# 22_Nvidia_CAN.net
KiCad netlist of a schematic drawn in Altium Designer
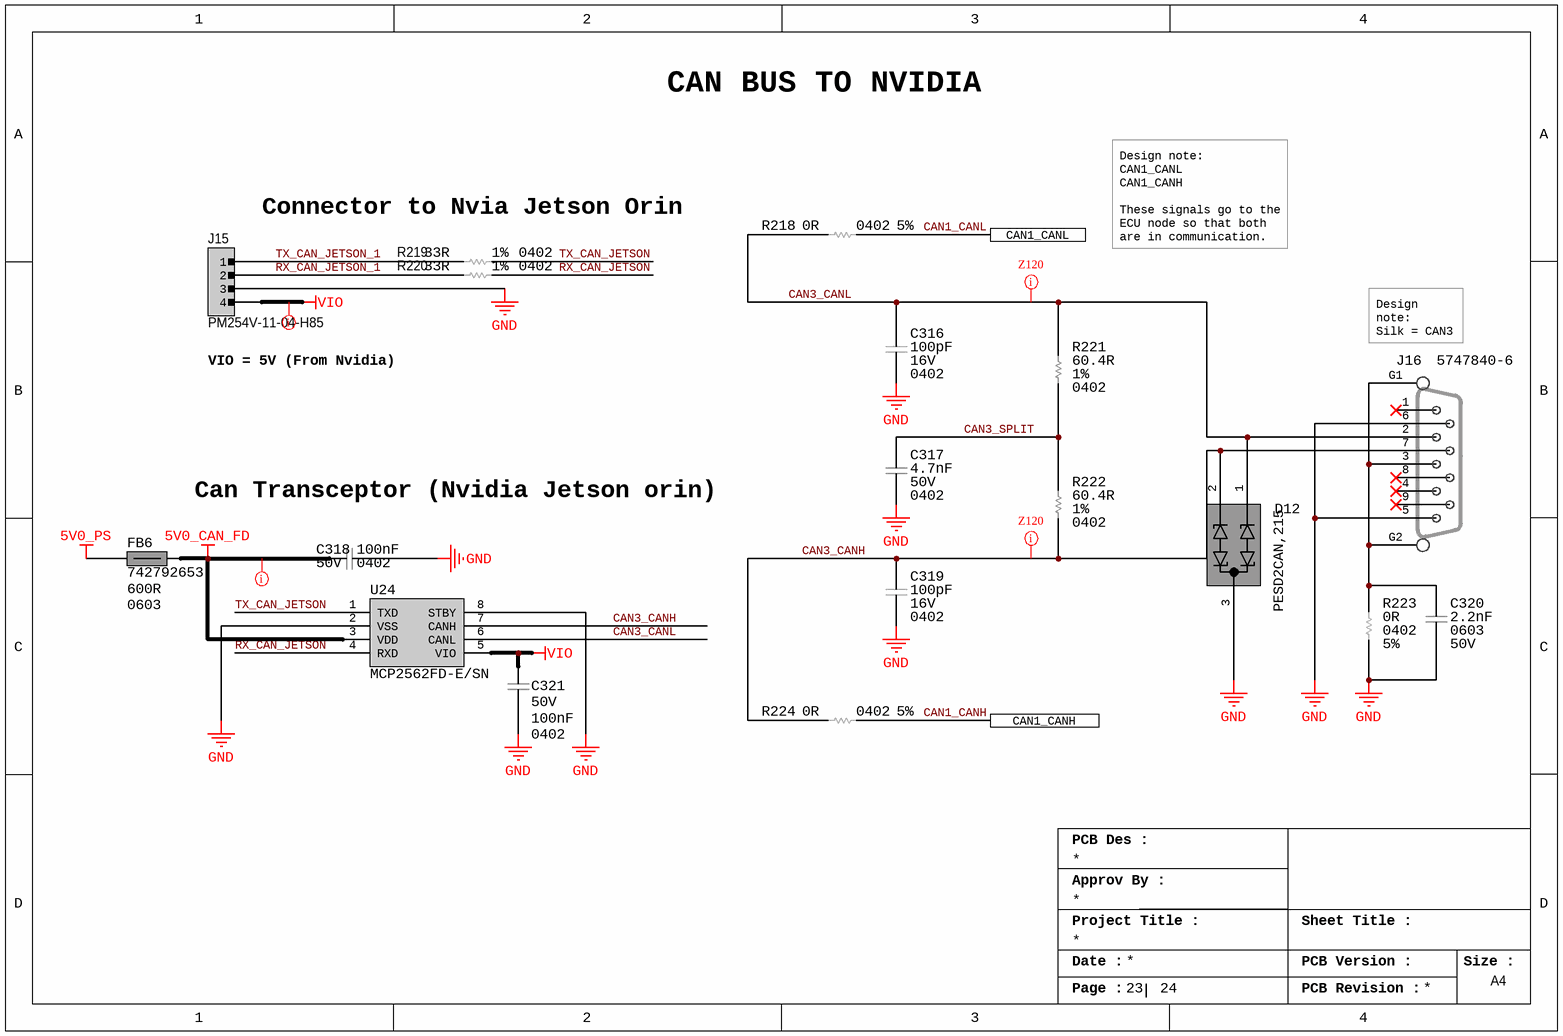
[diagram p0: 22_Nvidia_CAN.SchDoc]

(export (version "E")
  (design (tool "Eeschema 10.0.6"))
  (components
    (comp (ref "C316")
      (value "CC0402JRNPO7BN101")
      (footprint "CAP_0402_CAPC1005X05N")
      (description "0402 100 pF 16 V ±5 % Tolerance NP0 SMT Multilayer Ceramic Capacitor")
      (fields
        (field (name "MANUFACTURER") "Yageo")
        (field (name "TOLERANCE") "5%")
        (field (name "VOLTAGE RATING (DC)") "16V")
        (field (name "CAPACITANCE") "100pF")
        (field (name "CASE/PACKAGE") "0402")
      )
      (libsource (lib "Electronic Devices_LIB") (part "CAP_100PF_16V_NP0_0402"))
    )
    (comp (ref "C317")
      (value "GRM155R61H472KA01D")
      (footprint "CAP_0402_CAPC1005X05N")
      (description "Multilayer Ceramic Capacitor, 100 uF, 16 V, ± 20%, X5R, 1210 [3225 Metric]")
      (fields
        (field (name "MANUFACTURER") "Murata")
        (field (name "TOLERANCE") "10%")
        (field (name "VOLTAGE RATING") "50V")
        (field (name "CAPACITANCE") "4.7nF")
        (field (name "CASE/PACKAGE") "0402")
      )
      (libsource (lib "Electronic Devices_LIB") (part "CAP_4700PF_50V_X5R_0402"))
    )
    (comp (ref "C318")
      (value "GRM155R71H104KE14D")
      (footprint "CAP_0402_CAPC1005X05N")
      (description "Multilayer Ceramic Capacitor, 0.1 uF, 16 V, ± 10%, X7R, 0402 [1005 Metric]")
      (fields
        (field (name "MANUFACTURER") "Murata")
        (field (name "TOLERANCE") "10%")
        (field (name "VOLTAGE RATING") "50V")
        (field (name "CAPACITANCE") "100nF")
        (field (name "CASE/PACKAGE") "0402")
      )
      (libsource (lib "Electronic Devices_LIB") (part "CAP_100NF_50V_X7R_0402"))
    )
    (comp (ref "C319")
      (value "CC0402JRNPO7BN101")
      (footprint "CAP_0402_CAPC1005X05N")
      (description "0402 100 pF 16 V ±5 % Tolerance NP0 SMT Multilayer Ceramic Capacitor")
      (fields
        (field (name "MANUFACTURER") "Yageo")
        (field (name "TOLERANCE") "5%")
        (field (name "VOLTAGE RATING (DC)") "16V")
        (field (name "CAPACITANCE") "100pF")
        (field (name "CASE/PACKAGE") "0402")
      )
      (libsource (lib "Electronic Devices_LIB") (part "CAP_100PF_16V_NP0_0402"))
    )
    (comp (ref "C320")
      (value "GRM1885C1H222JA01D")
      (footprint "CAP_0603_CAPC1608X08N")
      (description "Multilayer Ceramic Capacitor, 2200 pF, 50 V, ï¿½ 5%, C0G (NP0), 0603 [1608 Metric]")
      (fields
        (field (name "MANUFACTURER") "Murata")
        (field (name "TOLERANCE") "5%")
        (field (name "CASE/PACKAGE") "0603")
        (field (name "VOLTAGE RATING") "50V")
        (field (name "CAPACITANCE") "2.2nF")
      )
      (libsource (lib "Electronic Devices_LIB") (part "CAP_2.2nF_50V_NP0_0402"))
    )
    (comp (ref "C321")
      (value "GRM155R71H104KE14D")
      (footprint "CAP_0402_CAPC1005X05N")
      (description "Multilayer Ceramic Capacitor, 0.1 uF, 16 V, ± 10%, X7R, 0402 [1005 Metric]")
      (fields
        (field (name "MANUFACTURER") "Murata")
        (field (name "TOLERANCE") "10%")
        (field (name "VOLTAGE RATING") "50V")
        (field (name "CAPACITANCE") "100nF")
        (field (name "CASE/PACKAGE") "0402")
      )
      (libsource (lib "Electronic Devices_LIB") (part "CAP_100NF_50V_X7R_0402"))
    )
    (comp (ref "D12")
      (value "PESD2CAN,215")
      (footprint "DIO_PESD2CAN,215")
      (description "5A 230W 41V 26.2V Bidirectional 24V SOT-23 ESD and Surge Protection (TVS/ESD) ROHS")
      (fields (field (name "MANUFACTURER") "Nexperia"))
      (libsource (lib "Electronic Devices_LIB") (part "DIO_TVS_41V_5A_PESD2CAN,215"))
    )
    (comp (ref "FB6")
      (value "742792653")
      (footprint "IND_0603_INDC1608X08N")
      (description "WE-CBF Ferrite Bead 0603 600Ohm 300mA ¦ Wurth Elektronik 742792653")
      (fields
        (field (name "MANUFACTURER") "Wurth Electronics")
        (field (name "TOLERANCE") "25%")
        (field (name "IMPEDANCE") "600R")
        (field (name "CASE CODE (IMPERIAL)") "0603")
      )
      (libsource (lib "Electronic Devices_LIB") (part "IND_FERRITE_BEADS_600R_300mA_0603_742792653"))
    )
    (comp (ref "J15")
      (value "PM254V-11-04-H85")
      (footprint "CONN_HEADER_FEM_4P")
      (description "2.54mm Plugin 4P Brass Straight 1x4P Plugin,P=2.54mm  Female Headers ROHS")
      (fields (field (name "MANUFACTURER") "XFCN") (field (name "JLCPCB PART NUMBER") "C541851"))
      (libsource (lib "Electronic Devices_LIB") (part "CONN_HEADER_FEMALE_4P_2.54mm_JLCPCB"))
    )
    (comp (ref "J16")
      (value "5747840-6")
      (footprint "TE_5747840-6")
      (description "D Subminiature Connector, 9 Contact(s), Male, 0.108 inch Pitch, Solder Terminal, #4-40, Plug")
      (fields (field (name "MANUFACTURER") "TE Connectivity"))
      (libsource (lib "Electronic Devices_LIB") (part "CONN_DB9_TEConnectivity_5747840-6"))
    )
    (comp (ref "R218")
      (value "ERJ-2GE0R00X")
      (footprint "RES_0402_RESC1005X04N")
      (description "SMD Chip Resistor, Jumper, 0 ohm, 100 mW, 0402 [1005 Metric], Thick Film, General Purpose")
      (fields
        (field (name "MANUFACTURER") "Panasonic")
        (field (name "CASE CODE (IMPERIAL)") "0402")
        (field (name "TOLERANCE") "5%")
        (field (name "RESISTANCE") "0R")
      )
      (libsource (lib "Electronic Devices_LIB") (part "RES_0R_5%_100mW_0402"))
    )
    (comp (ref "R219")
      (value "RC0402FR-0733RL")
      (footprint "RES_0402_RESC1005X04N")
      (description "SMD Chip Resistor, 33 Ohm, ± 1%, 62.5 mW, 0402 [1005 Metric], Thick Film, General Purpose")
      (fields
        (field (name "MANUFACTURER") "Yageo")
        (field (name "TOLERANCE") "1%")
        (field (name "RESISTANCE") "33R")
        (field (name "CASE/PACKAGE") "0402")
      )
      (libsource (lib "Electronic Devices_LIB") (part "RES_33R_1%_62.5mW_0402"))
    )
    (comp (ref "R220")
      (value "RC0402FR-0733RL")
      (footprint "RES_0402_RESC1005X04N")
      (description "SMD Chip Resistor, 33 Ohm, ± 1%, 62.5 mW, 0402 [1005 Metric], Thick Film, General Purpose")
      (fields
        (field (name "MANUFACTURER") "Yageo")
        (field (name "TOLERANCE") "1%")
        (field (name "RESISTANCE") "33R")
        (field (name "CASE/PACKAGE") "0402")
      )
      (libsource (lib "Electronic Devices_LIB") (part "RES_33R_1%_62.5mW_0402"))
    )
    (comp (ref "R221")
      (value "RK73H1ETTP60R4F")
      (footprint "RES_0402_RESC1005X04N")
      (description "Res Thick Film 0402 60.4 Ohm 1% 0.1W(1/10W) ±100ppm/C Pad SMD Automotive T/R")
      (fields
        (field (name "MANUFACTURER") "KOA Speer")
        (field (name "TOLERANCE") "1%")
        (field (name "RESISTANCE") "60.4R")
        (field (name "CASE/PACKAGE") "0402")
      )
      (libsource (lib "Electronic Devices_LIB") (part "RES_60.4R_1%_100mW_0402"))
    )
    (comp (ref "R222")
      (value "RK73H1ETTP60R4F")
      (footprint "RES_0402_RESC1005X04N")
      (description "Res Thick Film 0402 60.4 Ohm 1% 0.1W(1/10W) ±100ppm/C Pad SMD Automotive T/R")
      (fields
        (field (name "MANUFACTURER") "KOA Speer")
        (field (name "TOLERANCE") "1%")
        (field (name "RESISTANCE") "60.4R")
        (field (name "CASE/PACKAGE") "0402")
      )
      (libsource (lib "Electronic Devices_LIB") (part "RES_60.4R_1%_100mW_0402"))
    )
    (comp (ref "R223")
      (value "ERJ-2GE0R00X")
      (footprint "RES_0402_RESC1005X04N")
      (description "SMD Chip Resistor, Jumper, 0 ohm, 100 mW, 0402 [1005 Metric], Thick Film, General Purpose")
      (fields
        (field (name "MANUFACTURER") "Panasonic")
        (field (name "CASE CODE (IMPERIAL)") "0402")
        (field (name "TOLERANCE") "5%")
        (field (name "RESISTANCE") "0R")
      )
      (libsource (lib "Electronic Devices_LIB") (part "RES_0R_5%_100mW_0402"))
    )
    (comp (ref "R224")
      (value "ERJ-2GE0R00X")
      (footprint "RES_0402_RESC1005X04N")
      (description "SMD Chip Resistor, Jumper, 0 ohm, 100 mW, 0402 [1005 Metric], Thick Film, General Purpose")
      (fields
        (field (name "MANUFACTURER") "Panasonic")
        (field (name "CASE CODE (IMPERIAL)") "0402")
        (field (name "TOLERANCE") "5%")
        (field (name "RESISTANCE") "0R")
      )
      (libsource (lib "Electronic Devices_LIB") (part "RES_0R_5%_100mW_0402"))
    )
    (comp (ref "U24")
      (value "MCP2562FD-E/SN")
      (footprint "SOIC127P600X175-8N")
      (description "MCP2562 Series 5 V Surface Mount High-Speed CAN Transceiver - SOIC-8")
      (fields (field (name "MANUFACTURER") "Microchip"))
      (libsource (lib "Electronic Devices_LIB") (part "IC_TRANSCEIVER_CAN_MCP2562FD-E/SN"))
    )
  )
  (nets
    (net (code "1") (name "/CAN1_CANH") (class "Default")
      (node (ref "R224") (pin "2") (pinfunction "2_2") (pintype "passive"))
    )
    (net (code "2") (name "/CAN1_CANL") (class "Default")
      (node (ref "R218") (pin "2") (pinfunction "2_2") (pintype "passive"))
    )
    (net (code "3") (name "/CAN3_CANH") (class "Default")
      (node (ref "C319") (pin "2") (pinfunction "2_2") (pintype "passive"))
      (node (ref "D12") (pin "2") (pinfunction "C2_2") (pintype "passive"))
      (node (ref "J16") (pin "7") (pinfunction "7_7") (pintype "passive"))
      (node (ref "R222") (pin "1") (pinfunction "1_1") (pintype "passive"))
      (node (ref "R224") (pin "1") (pinfunction "1_1") (pintype "passive"))
      (node (ref "U24") (pin "7") (pinfunction "CANH_7") (pintype "passive"))
    )
    (net (code "4") (name "/CAN3_CANL") (class "Default")
      (node (ref "C316") (pin "2") (pinfunction "2_2") (pintype "passive"))
      (node (ref "D12") (pin "1") (pinfunction "C1_1") (pintype "passive"))
      (node (ref "J16") (pin "2") (pinfunction "2_2") (pintype "passive"))
      (node (ref "R218") (pin "1") (pinfunction "1_1") (pintype "passive"))
      (node (ref "R221") (pin "2") (pinfunction "2_2") (pintype "passive"))
      (node (ref "U24") (pin "6") (pinfunction "CANL_6") (pintype "passive"))
    )
    (net (code "5") (name "/CAN3_SPLIT") (class "Default")
      (node (ref "C317") (pin "2") (pinfunction "2_2") (pintype "passive"))
      (node (ref "R221") (pin "1") (pinfunction "1_1") (pintype "passive"))
      (node (ref "R222") (pin "2") (pinfunction "2_2") (pintype "passive"))
    )
    (net (code "6") (name "/RX_CAN_JETSON") (class "Default")
      (node (ref "R220") (pin "2") (pinfunction "2_2") (pintype "passive"))
      (node (ref "U24") (pin "4") (pinfunction "RXD_4") (pintype "passive"))
    )
    (net (code "7") (name "/RX_CAN_JETSON_1") (class "Default")
      (node (ref "J15") (pin "2") (pinfunction "2_2") (pintype "passive"))
      (node (ref "R220") (pin "1") (pinfunction "1_1") (pintype "passive"))
    )
    (net (code "8") (name "/TX_CAN_JETSON") (class "Default")
      (node (ref "R219") (pin "2") (pinfunction "2_2") (pintype "passive"))
      (node (ref "U24") (pin "1") (pinfunction "TXD_1") (pintype "passive"))
    )
    (net (code "9") (name "/TX_CAN_JETSON_1") (class "Default")
      (node (ref "J15") (pin "1") (pinfunction "1_1") (pintype "passive"))
      (node (ref "R219") (pin "1") (pinfunction "1_1") (pintype "passive"))
    )
    (net (code "10") (name "5V0_CAN_FD") (class "Default")
      (node (ref "C318") (pin "1") (pinfunction "1_1") (pintype "passive"))
      (node (ref "FB6") (pin "2") (pinfunction "2_2") (pintype "passive"))
      (node (ref "U24") (pin "3") (pinfunction "VDD_3") (pintype "passive"))
    )
    (net (code "11") (name "5V0_PS") (class "Default")
      (node (ref "FB6") (pin "1") (pinfunction "1_1") (pintype "passive"))
    )
    (net (code "12") (name "GND") (class "Default")
      (node (ref "C316") (pin "1") (pinfunction "1_1") (pintype "passive"))
      (node (ref "C317") (pin "1") (pinfunction "1_1") (pintype "passive"))
      (node (ref "C318") (pin "2") (pinfunction "2_2") (pintype "passive"))
      (node (ref "C319") (pin "1") (pinfunction "1_1") (pintype "passive"))
      (node (ref "C320") (pin "1") (pinfunction "1_1") (pintype "passive"))
      (node (ref "C321") (pin "2") (pinfunction "2_2") (pintype "passive"))
      (node (ref "D12") (pin "3") (pinfunction "CC_3") (pintype "passive"))
      (node (ref "J15") (pin "3") (pinfunction "3_3") (pintype "passive"))
      (node (ref "J16") (pin "5") (pinfunction "5_5") (pintype "passive"))
      (node (ref "J16") (pin "6") (pinfunction "6_6") (pintype "passive"))
      (node (ref "R223") (pin "1") (pinfunction "1_1") (pintype "passive"))
      (node (ref "U24") (pin "2") (pinfunction "VSS_2") (pintype "passive"))
      (node (ref "U24") (pin "8") (pinfunction "STBY_8") (pintype "passive"))
    )
    (net (code "13") (name "Net-(J16-G)") (class "Default")
      (node (ref "C320") (pin "2") (pinfunction "2_2") (pintype "passive"))
      (node (ref "J16") (pin "3") (pinfunction "3_3") (pintype "passive"))
      (node (ref "J16") (pin "G1") (pinfunction "G1_G1") (pintype "passive"))
      (node (ref "J16") (pin "G2") (pinfunction "G_G2") (pintype "passive"))
      (node (ref "R223") (pin "2") (pinfunction "2_2") (pintype "passive"))
    )
    (net (code "14") (name "VIO") (class "Default")
      (node (ref "C321") (pin "1") (pinfunction "1_1") (pintype "passive"))
      (node (ref "J15") (pin "4") (pinfunction "4_4") (pintype "passive"))
      (node (ref "U24") (pin "5") (pinfunction "VIO_5") (pintype "passive"))
    )
    (net (code "15") (name "unconnected-(J16-Pad1)") (class "Default")
      (node (ref "J16") (pin "1") (pinfunction "1_1") (pintype "passive+no_connect"))
    )
    (net (code "16") (name "unconnected-(J16-Pad4)") (class "Default")
      (node (ref "J16") (pin "4") (pinfunction "4_4") (pintype "passive+no_connect"))
    )
    (net (code "17") (name "unconnected-(J16-Pad8)") (class "Default")
      (node (ref "J16") (pin "8") (pinfunction "8_8") (pintype "passive+no_connect"))
    )
    (net (code "18") (name "unconnected-(J16-Pad9)") (class "Default")
      (node (ref "J16") (pin "9") (pinfunction "9_9") (pintype "passive+no_connect"))
    )
  )
)
